# Operant_Front_Bonsai_Large.net
KiCad netlist of a schematic drawn in EAGLE
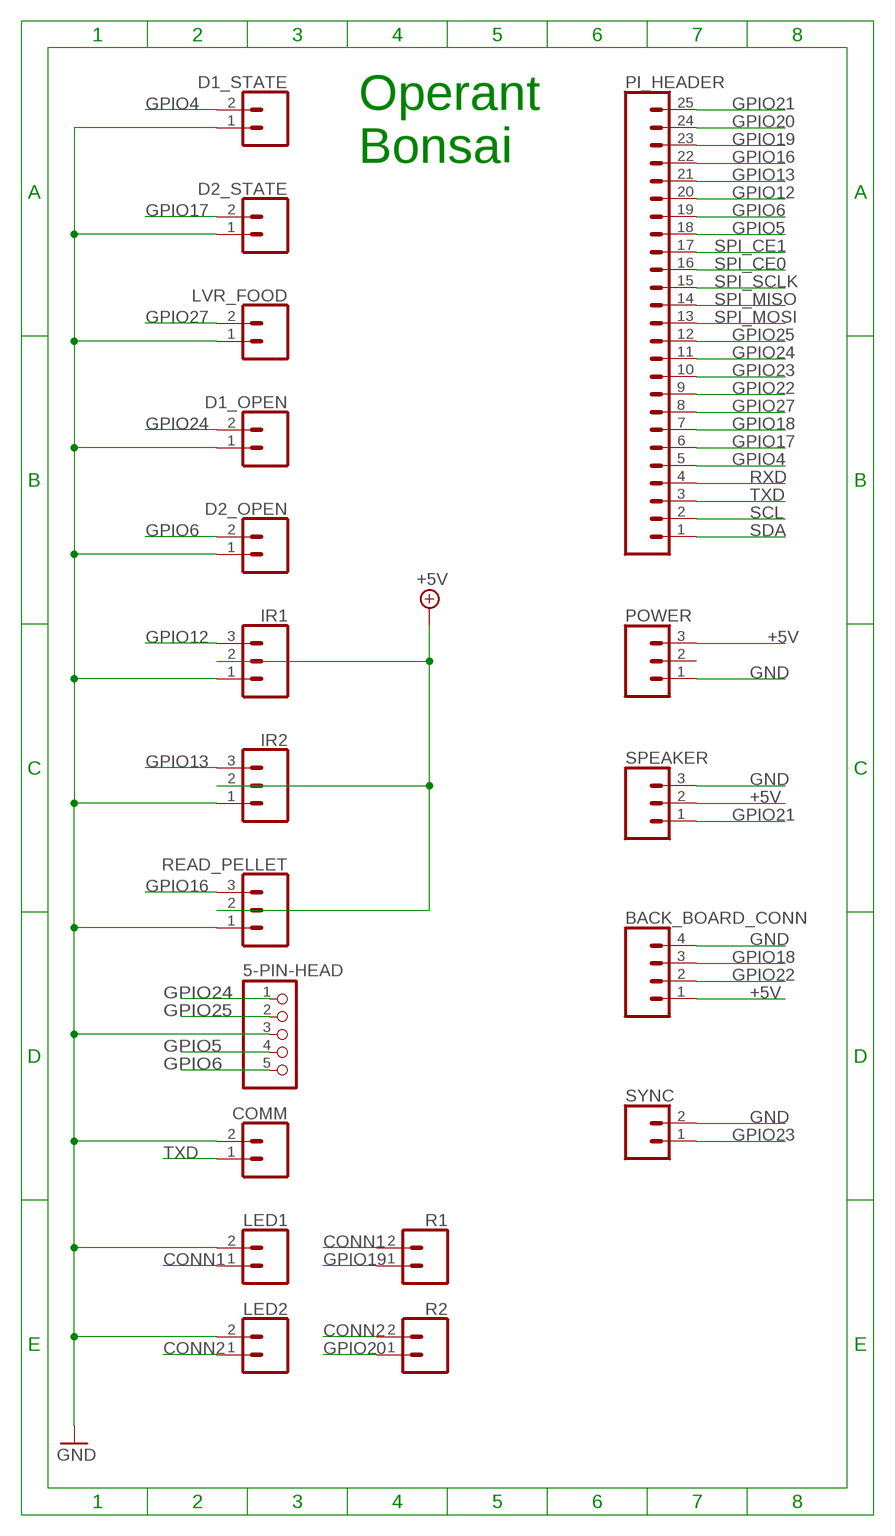
[diagram p0: schematic, sheet 1]

(export (version "E")
  (design (tool "Eeschema 10.0.6"))
  (components
    (comp (ref "5-PIN-HEAD")
      (value "PINHD-1X5")
      (footprint "eagle-import:1X05")
      (libsource (lib "eagle-import") (part "PINHD-1X5"))
    )
    (comp (ref "BACK_BOARD_CONN")
      (value "CONN_04JST-PTH")
      (footprint "eagle-import:JST-4-PTH")
      (libsource (lib "eagle-import") (part "CONN_04JST-PTH"))
    )
    (comp (ref "COMM")
      (value "CONN_02JST-PTH-2")
      (footprint "eagle-import:JST-2-PTH")
      (libsource (lib "eagle-import") (part "CONN_02JST-PTH-2"))
    )
    (comp (ref "D1_OPEN")
      (value "CONN_02JST-PTH-2")
      (footprint "eagle-import:JST-2-PTH")
      (libsource (lib "eagle-import") (part "CONN_02JST-PTH-2"))
    )
    (comp (ref "D1_STATE")
      (value "CONN_02JST-PTH-2")
      (footprint "eagle-import:JST-2-PTH")
      (libsource (lib "eagle-import") (part "CONN_02JST-PTH-2"))
    )
    (comp (ref "D2_OPEN")
      (value "CONN_02JST-PTH-2")
      (footprint "eagle-import:JST-2-PTH")
      (libsource (lib "eagle-import") (part "CONN_02JST-PTH-2"))
    )
    (comp (ref "D2_STATE")
      (value "CONN_02JST-PTH-2")
      (footprint "eagle-import:JST-2-PTH")
      (libsource (lib "eagle-import") (part "CONN_02JST-PTH-2"))
    )
    (comp (ref "IR1")
      (value "CONN_03JST-PTH")
      (footprint "eagle-import:JST-3-PTH")
      (libsource (lib "eagle-import") (part "CONN_03JST-PTH"))
    )
    (comp (ref "IR2")
      (value "CONN_03JST-PTH")
      (footprint "eagle-import:JST-3-PTH")
      (libsource (lib "eagle-import") (part "CONN_03JST-PTH"))
    )
    (comp (ref "LED1")
      (value "CONN_02")
      (footprint "eagle-import:1X02")
      (libsource (lib "eagle-import") (part "CONN_02"))
    )
    (comp (ref "LED2")
      (value "CONN_02")
      (footprint "eagle-import:1X02")
      (libsource (lib "eagle-import") (part "CONN_02"))
    )
    (comp (ref "LVR_FOOD")
      (value "CONN_02JST-PTH-2")
      (footprint "eagle-import:JST-2-PTH")
      (libsource (lib "eagle-import") (part "CONN_02JST-PTH-2"))
    )
    (comp (ref "PI_HEADER")
      (value "CONN_25")
      (footprint "eagle-import:1X25")
      (libsource (lib "eagle-import") (part "CONN_25"))
    )
    (comp (ref "POWER")
      (value "CONN_03")
      (footprint "eagle-import:1X03")
      (libsource (lib "eagle-import") (part "CONN_03"))
    )
    (comp (ref "R1")
      (value "CONN_02")
      (footprint "eagle-import:1X02")
      (libsource (lib "eagle-import") (part "CONN_02"))
    )
    (comp (ref "R2")
      (value "CONN_02")
      (footprint "eagle-import:1X02")
      (libsource (lib "eagle-import") (part "CONN_02"))
    )
    (comp (ref "READ_PELLET")
      (value "CONN_03JST-PTH")
      (footprint "eagle-import:JST-3-PTH")
      (libsource (lib "eagle-import") (part "CONN_03JST-PTH"))
    )
    (comp (ref "SPEAKER")
      (value "CONN_03JST-PTH")
      (footprint "eagle-import:JST-3-PTH")
      (libsource (lib "eagle-import") (part "CONN_03JST-PTH"))
    )
    (comp (ref "SYNC")
      (value "CONN_02")
      (footprint "eagle-import:1X02")
      (libsource (lib "eagle-import") (part "CONN_02"))
    )
  )
  (nets
    (net (code "1") (name "+5V") (class "Default")
      (node (ref "BACK_BOARD_CONN") (pin "1") (pinfunction "1_1") (pintype "passive"))
      (node (ref "IR1") (pin "2") (pinfunction "2_2") (pintype "passive"))
      (node (ref "IR2") (pin "2") (pinfunction "2_2") (pintype "passive"))
      (node (ref "POWER") (pin "3") (pinfunction "3_3") (pintype "passive"))
      (node (ref "READ_PELLET") (pin "2") (pinfunction "2_2") (pintype "passive"))
      (node (ref "SPEAKER") (pin "2") (pinfunction "2_2") (pintype "passive"))
    )
    (net (code "2") (name "/CONN1") (class "Default")
      (node (ref "LED1") (pin "1") (pinfunction "1_1") (pintype "passive"))
      (node (ref "R1") (pin "2") (pinfunction "2_2") (pintype "passive"))
    )
    (net (code "3") (name "/CONN2") (class "Default")
      (node (ref "LED2") (pin "1") (pinfunction "1_1") (pintype "passive"))
      (node (ref "R2") (pin "2") (pinfunction "2_2") (pintype "passive"))
    )
    (net (code "4") (name "/GPIO4") (class "Default")
      (node (ref "D1_STATE") (pin "2") (pinfunction "2_2") (pintype "passive"))
      (node (ref "PI_HEADER") (pin "5") (pinfunction "5_5") (pintype "passive"))
    )
    (net (code "5") (name "/GPIO5") (class "Default")
      (node (ref "5-PIN-HEAD") (pin "4") (pinfunction "4_4") (pintype "passive"))
      (node (ref "PI_HEADER") (pin "18") (pinfunction "18_18") (pintype "passive"))
    )
    (net (code "6") (name "/GPIO6") (class "Default")
      (node (ref "5-PIN-HEAD") (pin "5") (pinfunction "5_5") (pintype "passive"))
      (node (ref "D2_OPEN") (pin "2") (pinfunction "2_2") (pintype "passive"))
      (node (ref "PI_HEADER") (pin "19") (pinfunction "19_19") (pintype "passive"))
    )
    (net (code "7") (name "/GPIO12") (class "Default")
      (node (ref "IR1") (pin "3") (pinfunction "3_3") (pintype "passive"))
      (node (ref "PI_HEADER") (pin "20") (pinfunction "20_20") (pintype "passive"))
    )
    (net (code "8") (name "/GPIO13") (class "Default")
      (node (ref "IR2") (pin "3") (pinfunction "3_3") (pintype "passive"))
      (node (ref "PI_HEADER") (pin "21") (pinfunction "21_21") (pintype "passive"))
    )
    (net (code "9") (name "/GPIO16") (class "Default")
      (node (ref "PI_HEADER") (pin "22") (pinfunction "22_22") (pintype "passive"))
      (node (ref "READ_PELLET") (pin "3") (pinfunction "3_3") (pintype "passive"))
    )
    (net (code "10") (name "/GPIO17") (class "Default")
      (node (ref "D2_STATE") (pin "2") (pinfunction "2_2") (pintype "passive"))
      (node (ref "PI_HEADER") (pin "6") (pinfunction "6_6") (pintype "passive"))
    )
    (net (code "11") (name "/GPIO18") (class "Default")
      (node (ref "BACK_BOARD_CONN") (pin "3") (pinfunction "3_3") (pintype "passive"))
      (node (ref "PI_HEADER") (pin "7") (pinfunction "7_7") (pintype "passive"))
    )
    (net (code "12") (name "/GPIO19") (class "Default")
      (node (ref "PI_HEADER") (pin "23") (pinfunction "23_23") (pintype "passive"))
      (node (ref "R1") (pin "1") (pinfunction "1_1") (pintype "passive"))
    )
    (net (code "13") (name "/GPIO20") (class "Default")
      (node (ref "PI_HEADER") (pin "24") (pinfunction "24_24") (pintype "passive"))
      (node (ref "R2") (pin "1") (pinfunction "1_1") (pintype "passive"))
    )
    (net (code "14") (name "/GPIO21") (class "Default")
      (node (ref "PI_HEADER") (pin "25") (pinfunction "25_25") (pintype "passive"))
      (node (ref "SPEAKER") (pin "1") (pinfunction "1_1") (pintype "passive"))
    )
    (net (code "15") (name "/GPIO22") (class "Default")
      (node (ref "BACK_BOARD_CONN") (pin "2") (pinfunction "2_2") (pintype "passive"))
      (node (ref "PI_HEADER") (pin "9") (pinfunction "9_9") (pintype "passive"))
    )
    (net (code "16") (name "/GPIO23") (class "Default")
      (node (ref "PI_HEADER") (pin "10") (pinfunction "10_10") (pintype "passive"))
      (node (ref "SYNC") (pin "1") (pinfunction "1_1") (pintype "passive"))
    )
    (net (code "17") (name "/GPIO24") (class "Default")
      (node (ref "5-PIN-HEAD") (pin "1") (pinfunction "1_1") (pintype "passive"))
      (node (ref "D1_OPEN") (pin "2") (pinfunction "2_2") (pintype "passive"))
      (node (ref "PI_HEADER") (pin "11") (pinfunction "11_11") (pintype "passive"))
    )
    (net (code "18") (name "/GPIO25") (class "Default")
      (node (ref "5-PIN-HEAD") (pin "2") (pinfunction "2_2") (pintype "passive"))
      (node (ref "PI_HEADER") (pin "12") (pinfunction "12_12") (pintype "passive"))
    )
    (net (code "19") (name "/GPIO27") (class "Default")
      (node (ref "LVR_FOOD") (pin "2") (pinfunction "2_2") (pintype "passive"))
      (node (ref "PI_HEADER") (pin "8") (pinfunction "8_8") (pintype "passive"))
    )
    (net (code "20") (name "/RXD") (class "Default")
      (node (ref "PI_HEADER") (pin "4") (pinfunction "4_4") (pintype "passive"))
    )
    (net (code "21") (name "/SCL") (class "Default")
      (node (ref "PI_HEADER") (pin "2") (pinfunction "2_2") (pintype "passive"))
    )
    (net (code "22") (name "/SDA") (class "Default")
      (node (ref "PI_HEADER") (pin "1") (pinfunction "1_1") (pintype "passive"))
    )
    (net (code "23") (name "/SPI_CE0") (class "Default")
      (node (ref "PI_HEADER") (pin "16") (pinfunction "16_16") (pintype "passive"))
    )
    (net (code "24") (name "/SPI_CE1") (class "Default")
      (node (ref "PI_HEADER") (pin "17") (pinfunction "17_17") (pintype "passive"))
    )
    (net (code "25") (name "/SPI_MISO") (class "Default")
      (node (ref "PI_HEADER") (pin "14") (pinfunction "14_14") (pintype "passive"))
    )
    (net (code "26") (name "/SPI_MOSI") (class "Default")
      (node (ref "PI_HEADER") (pin "13") (pinfunction "13_13") (pintype "passive"))
    )
    (net (code "27") (name "/SPI_SCLK") (class "Default")
      (node (ref "PI_HEADER") (pin "15") (pinfunction "15_15") (pintype "passive"))
    )
    (net (code "28") (name "/TXD") (class "Default")
      (node (ref "COMM") (pin "1") (pinfunction "1_1") (pintype "passive"))
      (node (ref "PI_HEADER") (pin "3") (pinfunction "3_3") (pintype "passive"))
    )
    (net (code "29") (name "GND") (class "Default")
      (node (ref "5-PIN-HEAD") (pin "3") (pinfunction "3_3") (pintype "passive"))
      (node (ref "BACK_BOARD_CONN") (pin "4") (pinfunction "4_4") (pintype "passive"))
      (node (ref "COMM") (pin "2") (pinfunction "2_2") (pintype "passive"))
      (node (ref "D1_OPEN") (pin "1") (pinfunction "1_1") (pintype "passive"))
      (node (ref "D1_STATE") (pin "1") (pinfunction "1_1") (pintype "passive"))
      (node (ref "D2_OPEN") (pin "1") (pinfunction "1_1") (pintype "passive"))
      (node (ref "D2_STATE") (pin "1") (pinfunction "1_1") (pintype "passive"))
      (node (ref "IR1") (pin "1") (pinfunction "1_1") (pintype "passive"))
      (node (ref "IR2") (pin "1") (pinfunction "1_1") (pintype "passive"))
      (node (ref "LED1") (pin "2") (pinfunction "2_2") (pintype "passive"))
      (node (ref "LED2") (pin "2") (pinfunction "2_2") (pintype "passive"))
      (node (ref "LVR_FOOD") (pin "1") (pinfunction "1_1") (pintype "passive"))
      (node (ref "POWER") (pin "1") (pinfunction "1_1") (pintype "passive"))
      (node (ref "READ_PELLET") (pin "1") (pinfunction "1_1") (pintype "passive"))
      (node (ref "SPEAKER") (pin "3") (pinfunction "3_3") (pintype "passive"))
      (node (ref "SYNC") (pin "2") (pinfunction "2_2") (pintype "passive"))
    )
    (net (code "30") (name "unconnected-(POWER-Pad2)") (class "Default")
      (node (ref "POWER") (pin "2") (pinfunction "2_2") (pintype "passive"))
    )
  )
)
